# ArduinoRadioPC68XL.net
KiCad netlist of a schematic drawn in EAGLE
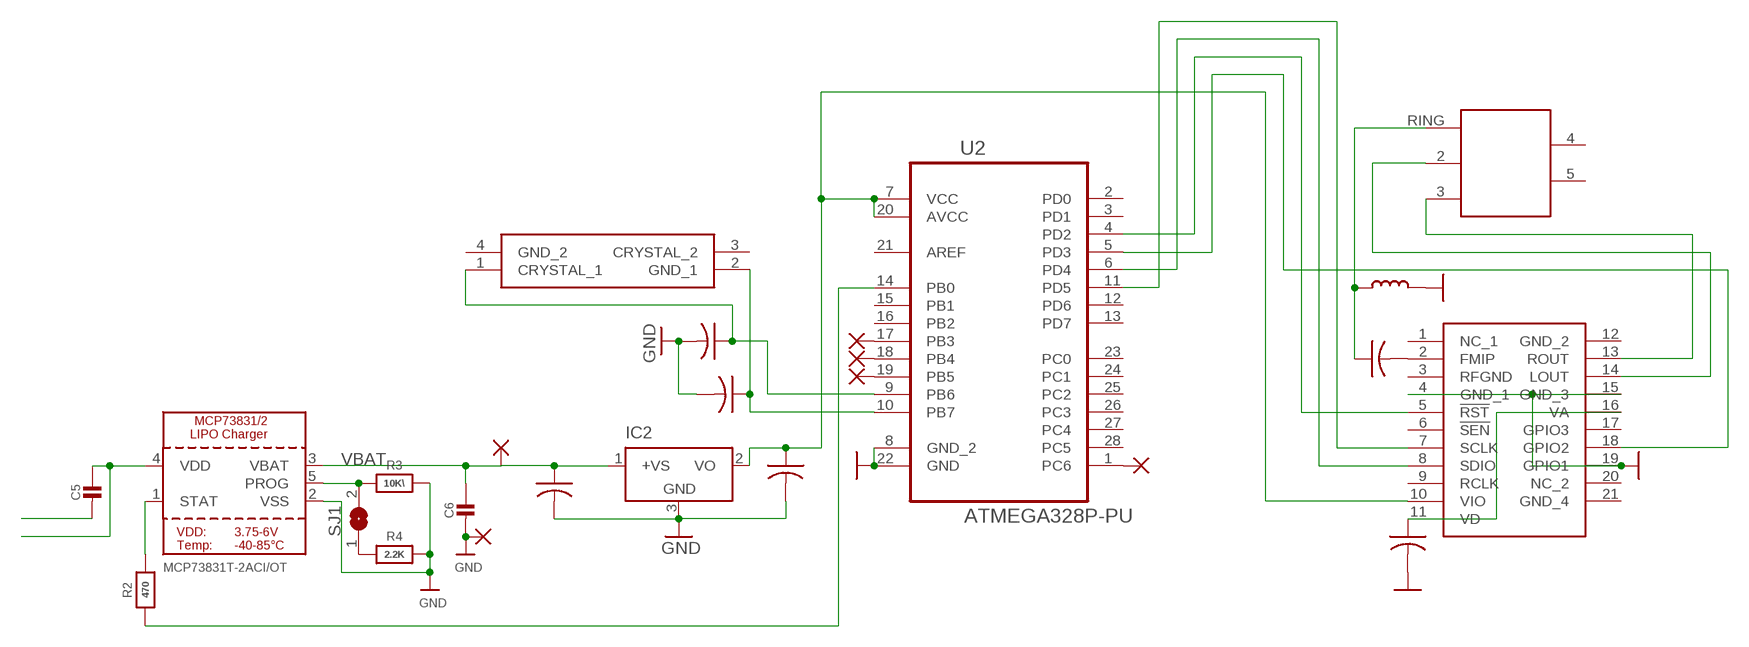
[diagram p0: schematic, sheet 1]

(export (version "E")
  (design (tool "Eeschema 10.0.6"))
  (components
    (comp (ref "C1")
      (value "10pF")
      (footprint "eagle-import:C0402")
      (libsource (lib "eagle-import") (part "rcl_334_C-USC0402"))
    )
    (comp (ref "C2")
      (value "10pF")
      (footprint "eagle-import:C0402")
      (libsource (lib "eagle-import") (part "rcl_334_C-USC0402"))
    )
    (comp (ref "C3")
      (value "47uf")
      (footprint "eagle-import:C1206")
      (libsource (lib "eagle-import") (part "better14pin_C-USC1206"))
    )
    (comp (ref "C4")
      (value "47uF")
      (footprint "eagle-import:C1206")
      (libsource (lib "eagle-import") (part "better14pin_C-USC1206"))
    )
    (comp (ref "C5")
      (value "10µF")
      (footprint "eagle-import:0805-NO@1")
      (libsource (lib "eagle-import") (part "CAP_CERAMIC0805-NOOUTLINE"))
    )
    (comp (ref "C6")
      (value "10µF")
      (footprint "eagle-import:0805-NO@1")
      (libsource (lib "eagle-import") (part "CAP_CERAMIC0805-NOOUTLINE"))
    )
    (comp (ref "C7")
      (value "22nF")
      (footprint "eagle-import:C0603")
      (libsource (lib "eagle-import") (part "C-USC0603"))
    )
    (comp (ref "C8")
      (value "100pF")
      (footprint "eagle-import:C1206")
      (libsource (lib "eagle-import") (part "C-USC1206"))
    )
    (comp (ref "IC2")
      (value "LM50")
      (footprint "eagle-import:SOT23")
      (libsource (lib "eagle-import") (part "LM50"))
    )
    (comp (ref "IC3")
      (value "SI4703-C19-GM")
      (footprint "eagle-import:SI4703C19GM")
      (fields
        (field (name "MANUFACTURER_PART_NUMBER") "Si4703-C19-GM")
        (field (name "MOUSER_PART_NUMBER") "634-SI4703-C19-GM")
      )
      (libsource (lib "eagle-import") (part "SI4703-C19-GM"))
    )
    (comp (ref "L1")
      (value "L_0603")
      (footprint "eagle-import:L0603")
      (libsource (lib "eagle-import") (part "L_0603"))
    )
    (comp (ref "PAD1")
      (value "WIREPADSMD1,27-254")
      (footprint "eagle-import:SMD1,27-2,54")
      (libsource (lib "eagle-import") (part "WIREPADSMD1,27-254"))
    )
    (comp (ref "PAD2")
      (value "WIREPADSMD1,27-254")
      (footprint "eagle-import:SMD1,27-2,54")
      (libsource (lib "eagle-import") (part "WIREPADSMD1,27-254"))
    )
    (comp (ref "PAD3")
      (value "SMD2")
      (footprint "eagle-import:SMD1,27-2,54")
      (libsource (lib "eagle-import") (part "SMD2"))
    )
    (comp (ref "PAD4")
      (value "SMD2")
      (footprint "eagle-import:SMD1,27-2,54")
      (libsource (lib "eagle-import") (part "SMD2"))
    )
    (comp (ref "PAD5")
      (value "SMD2")
      (footprint "eagle-import:SMD1,27-2,54")
      (libsource (lib "eagle-import") (part "SMD2"))
    )
    (comp (ref "PAD6")
      (value "SMD2")
      (footprint "eagle-import:SMD1,27-2,54")
      (libsource (lib "eagle-import") (part "SMD2"))
    )
    (comp (ref "R2")
      (value "470")
      (footprint "eagle-import:0603-NO")
      (libsource (lib "eagle-import") (part "RESISTOR_0603_NOOUT"))
    )
    (comp (ref "R3")
      (value "10K\\")
      (footprint "eagle-import:0603-NO")
      (libsource (lib "eagle-import") (part "RESISTOR_0603_NOOUT"))
    )
    (comp (ref "R4")
      (value "2.2K")
      (footprint "eagle-import:0603-NO")
      (libsource (lib "eagle-import") (part "RESISTOR_0603_NOOUT"))
    )
    (comp (ref "SJ1")
      (value "SOLDERJUMPER")
      (footprint "eagle-import:SOLDERJUMPER_ARROW_NOPASTE")
      (libsource (lib "eagle-import") (part "SOLDERJUMPER"))
    )
    (comp (ref "U$1")
      (value "STX-3542-5N-G-TR")
      (footprint "eagle-import:STX-3542-5N-G-TR")
      (libsource (lib "eagle-import") (part "STX-3542-5N-G-TR"))
    )
    (comp (ref "U1")
      (value "MCP73831T-2ACI/OT")
      (footprint "eagle-import:SOT23-5")
      (libsource (lib "eagle-import") (part "MCP73831/2"))
    )
    (comp (ref "U2")
      (value "ATMEGA328P-PU")
      (footprint "eagle-import:DIP254P762X457-28")
      (fields (field (name "MF") "Microchip"))
      (libsource (lib "eagle-import") (part "ATMEGA328P-PU"))
    )
    (comp (ref "Y1")
      (value "ABM3B-8.000MHZ-10-1-U-T")
      (footprint "eagle-import:ABM3B")
      (fields (field (name "MOUSER_PART_NUMBER") "815-ABM3B8MHZ101UT"))
      (libsource (lib "eagle-import") (part "ABM3B-8.000MHZ-10-1-U-T"))
    )
  )
  (nets
    (net (code "1") (name "/STAT") (class "Default")
      (node (ref "R2") (pin "1") (pinfunction "1_1") (pintype "passive"))
      (node (ref "R2") (pin "2") (pinfunction "2_2") (pintype "passive"))
      (node (ref "U1") (pin "1") (pinfunction "STAT_1") (pintype "output"))
      (node (ref "U2") (pin "14") (pinfunction "PB0_14") (pintype "bidirectional"))
    )
    (net (code "2") (name "/VBAT") (class "Default")
      (node (ref "C3") (pin "1") (pinfunction "1_1") (pintype "passive"))
      (node (ref "C6") (pin "1") (pinfunction "1_1") (pintype "passive"))
      (node (ref "C7") (pin "1") (pinfunction "1_1") (pintype "passive"))
      (node (ref "IC2") (pin "1") (pinfunction "+VS_1") (pintype "input"))
      (node (ref "IC3") (pin "11") (pinfunction "VD_11") (pintype "bidirectional"))
      (node (ref "IC3") (pin "16") (pinfunction "VA_16") (pintype "bidirectional"))
      (node (ref "PAD1") (pin "1") (pinfunction "P_1") (pintype "passive"))
      (node (ref "U1") (pin "3") (pinfunction "VBAT_3") (pintype "power_in"))
    )
    (net (code "3") (name "GND") (class "Default")
      (node (ref "C1") (pin "2") (pinfunction "2_2") (pintype "passive"))
      (node (ref "C2") (pin "2") (pinfunction "2_2") (pintype "passive"))
      (node (ref "C3") (pin "2") (pinfunction "2_2") (pintype "passive"))
      (node (ref "C4") (pin "2") (pinfunction "2_2") (pintype "passive"))
      (node (ref "C5") (pin "2") (pinfunction "2_2") (pintype "passive"))
      (node (ref "C6") (pin "2") (pinfunction "2_2") (pintype "passive"))
      (node (ref "C7") (pin "2") (pinfunction "2_2") (pintype "passive"))
      (node (ref "IC2") (pin "3") (pinfunction "GND_3") (pintype "power_in"))
      (node (ref "IC3") (pin "15") (pinfunction "GND_3_15") (pintype "bidirectional"))
      (node (ref "IC3") (pin "19") (pinfunction "GPIO1_19") (pintype "bidirectional"))
      (node (ref "IC3") (pin "4") (pinfunction "GND_1_4") (pintype "bidirectional"))
      (node (ref "L1") (pin "1") (pinfunction "1_1") (pintype "passive"))
      (node (ref "PAD2") (pin "1") (pinfunction "P_1") (pintype "passive"))
      (node (ref "R3") (pin "2") (pinfunction "2_2") (pintype "passive"))
      (node (ref "R4") (pin "2") (pinfunction "2_2") (pintype "passive"))
      (node (ref "U1") (pin "2") (pinfunction "VSS_2") (pintype "power_in"))
      (node (ref "U2") (pin "22") (pinfunction "GND_22") (pintype "passive"))
      (node (ref "U2") (pin "8") (pinfunction "GND_2_8") (pintype "passive"))
    )
    (net (code "4") (name "Net-(C8-Pad1)") (class "Default")
      (node (ref "C8") (pin "1") (pinfunction "1_1") (pintype "passive"))
      (node (ref "L1") (pin "2") (pinfunction "2_2") (pintype "passive"))
      (node (ref "U$1") (pin "RING") (pinfunction "RING_RING") (pintype "bidirectional"))
    )
    (net (code "5") (name "Net-(IC2-VO)") (class "Default")
      (node (ref "C4") (pin "1") (pinfunction "1_1") (pintype "passive"))
      (node (ref "IC2") (pin "2") (pinfunction "VO_2") (pintype "input"))
      (node (ref "IC3") (pin "10") (pinfunction "VIO_10") (pintype "bidirectional"))
      (node (ref "U2") (pin "20") (pinfunction "AVCC_20") (pintype "power_in"))
      (node (ref "U2") (pin "7") (pinfunction "VCC_7") (pintype "power_in"))
    )
    (net (code "6") (name "Net-(IC3-FMIP)") (class "Default")
      (node (ref "C8") (pin "2") (pinfunction "2_2") (pintype "passive"))
      (node (ref "IC3") (pin "2") (pinfunction "FMIP_2") (pintype "bidirectional"))
    )
    (net (code "7") (name "Net-(IC3-GPIO2)") (class "Default")
      (node (ref "IC3") (pin "18") (pinfunction "GPIO2_18") (pintype "bidirectional"))
      (node (ref "U2") (pin "5") (pinfunction "PD3_5") (pintype "bidirectional"))
    )
    (net (code "8") (name "Net-(IC3-LOUT)") (class "Default")
      (node (ref "IC3") (pin "14") (pinfunction "LOUT_14") (pintype "bidirectional"))
      (node (ref "U$1") (pin "2") (pinfunction "2_2") (pintype "bidirectional"))
    )
    (net (code "9") (name "Net-(IC3-ROUT)") (class "Default")
      (node (ref "IC3") (pin "13") (pinfunction "ROUT_13") (pintype "bidirectional"))
      (node (ref "U$1") (pin "3") (pinfunction "3_3") (pintype "bidirectional"))
    )
    (net (code "10") (name "Net-(IC3-SCLK)") (class "Default")
      (node (ref "IC3") (pin "7") (pinfunction "SCLK_7") (pintype "bidirectional"))
      (node (ref "U2") (pin "11") (pinfunction "PD5_11") (pintype "bidirectional"))
    )
    (net (code "11") (name "Net-(IC3-SDIO)") (class "Default")
      (node (ref "IC3") (pin "8") (pinfunction "SDIO_8") (pintype "bidirectional"))
      (node (ref "U2") (pin "6") (pinfunction "PD4_6") (pintype "bidirectional"))
    )
    (net (code "12") (name "Net-(IC3-~{RST})") (class "Default")
      (node (ref "IC3") (pin "5") (pinfunction "~{RST}_5") (pintype "bidirectional"))
      (node (ref "U2") (pin "4") (pinfunction "PD2_4") (pintype "bidirectional"))
    )
    (net (code "13") (name "Net-(PAD3-P)") (class "Default")
      (node (ref "PAD3") (pin "1") (pinfunction "P_1") (pintype "passive"))
      (node (ref "U2") (pin "1") (pinfunction "PC6_1") (pintype "bidirectional"))
    )
    (net (code "14") (name "Net-(PAD4-P)") (class "Default")
      (node (ref "PAD4") (pin "1") (pinfunction "P_1") (pintype "passive"))
      (node (ref "U2") (pin "19") (pinfunction "PB5_19") (pintype "bidirectional"))
    )
    (net (code "15") (name "Net-(PAD5-P)") (class "Default")
      (node (ref "PAD5") (pin "1") (pinfunction "P_1") (pintype "passive"))
      (node (ref "U2") (pin "18") (pinfunction "PB4_18") (pintype "bidirectional"))
    )
    (net (code "16") (name "Net-(PAD6-P)") (class "Default")
      (node (ref "PAD6") (pin "1") (pinfunction "P_1") (pintype "passive"))
      (node (ref "U2") (pin "17") (pinfunction "PB3_17") (pintype "bidirectional"))
    )
    (net (code "17") (name "Net-(R4-Pad1)") (class "Default")
      (node (ref "R4") (pin "1") (pinfunction "1_1") (pintype "passive"))
      (node (ref "SJ1") (pin "1") (pinfunction "1_1") (pintype "passive"))
    )
    (net (code "18") (name "Net-(U1-PROG)") (class "Default")
      (node (ref "R3") (pin "1") (pinfunction "1_1") (pintype "passive"))
      (node (ref "SJ1") (pin "2") (pinfunction "2_2") (pintype "passive"))
      (node (ref "U1") (pin "5") (pinfunction "PROG_5") (pintype "input"))
    )
    (net (code "19") (name "Net-(U1-VDD)") (class "Default")
      (node (ref "C5") (pin "1") (pinfunction "1_1") (pintype "passive"))
      (node (ref "U1") (pin "4") (pinfunction "VDD_4") (pintype "power_in"))
    )
    (net (code "20") (name "Net-(U2-PB6)") (class "Default")
      (node (ref "C2") (pin "1") (pinfunction "1_1") (pintype "passive"))
      (node (ref "U2") (pin "9") (pinfunction "PB6_9") (pintype "bidirectional"))
      (node (ref "Y1") (pin "1") (pinfunction "CRYSTAL_1_1") (pintype "bidirectional"))
    )
    (net (code "21") (name "Net-(U2-PB7)") (class "Default")
      (node (ref "C1") (pin "1") (pinfunction "1_1") (pintype "passive"))
      (node (ref "U2") (pin "10") (pinfunction "PB7_10") (pintype "bidirectional"))
      (node (ref "Y1") (pin "2") (pinfunction "GND_1_2") (pintype "bidirectional"))
    )
    (net (code "22") (name "unconnected-(IC3-GND_2-Pad12)") (class "Default")
      (node (ref "IC3") (pin "12") (pinfunction "GND_2_12") (pintype "bidirectional"))
    )
    (net (code "23") (name "unconnected-(IC3-GND_4-Pad21)") (class "Default")
      (node (ref "IC3") (pin "21") (pinfunction "GND_4_21") (pintype "bidirectional"))
    )
    (net (code "24") (name "unconnected-(IC3-GPIO3-Pad17)") (class "Default")
      (node (ref "IC3") (pin "17") (pinfunction "GPIO3_17") (pintype "bidirectional"))
    )
    (net (code "25") (name "unconnected-(IC3-NC_1-Pad1)") (class "Default")
      (node (ref "IC3") (pin "1") (pinfunction "NC_1_1") (pintype "bidirectional"))
    )
    (net (code "26") (name "unconnected-(IC3-NC_2-Pad20)") (class "Default")
      (node (ref "IC3") (pin "20") (pinfunction "NC_2_20") (pintype "bidirectional"))
    )
    (net (code "27") (name "unconnected-(IC3-RCLK-Pad9)") (class "Default")
      (node (ref "IC3") (pin "9") (pinfunction "RCLK_9") (pintype "bidirectional"))
    )
    (net (code "28") (name "unconnected-(IC3-RFGND-Pad3)") (class "Default")
      (node (ref "IC3") (pin "3") (pinfunction "RFGND_3") (pintype "bidirectional"))
    )
    (net (code "29") (name "unconnected-(IC3-~{SEN}-Pad6)") (class "Default")
      (node (ref "IC3") (pin "6") (pinfunction "~{SEN}_6") (pintype "bidirectional"))
    )
    (net (code "30") (name "unconnected-(U$1-Pad4)") (class "Default")
      (node (ref "U$1") (pin "4") (pinfunction "4_4") (pintype "bidirectional"))
    )
    (net (code "31") (name "unconnected-(U$1-Pad5)") (class "Default")
      (node (ref "U$1") (pin "5") (pinfunction "5_5") (pintype "bidirectional"))
    )
    (net (code "32") (name "unconnected-(U2-AREF-Pad21)") (class "Default")
      (node (ref "U2") (pin "21") (pinfunction "AREF_21") (pintype "input"))
    )
    (net (code "33") (name "unconnected-(U2-PB1-Pad15)") (class "Default")
      (node (ref "U2") (pin "15") (pinfunction "PB1_15") (pintype "bidirectional"))
    )
    (net (code "34") (name "unconnected-(U2-PB2-Pad16)") (class "Default")
      (node (ref "U2") (pin "16") (pinfunction "PB2_16") (pintype "bidirectional"))
    )
    (net (code "35") (name "unconnected-(U2-PC0-Pad23)") (class "Default")
      (node (ref "U2") (pin "23") (pinfunction "PC0_23") (pintype "bidirectional"))
    )
    (net (code "36") (name "unconnected-(U2-PC1-Pad24)") (class "Default")
      (node (ref "U2") (pin "24") (pinfunction "PC1_24") (pintype "bidirectional"))
    )
    (net (code "37") (name "unconnected-(U2-PC2-Pad25)") (class "Default")
      (node (ref "U2") (pin "25") (pinfunction "PC2_25") (pintype "bidirectional"))
    )
    (net (code "38") (name "unconnected-(U2-PC3-Pad26)") (class "Default")
      (node (ref "U2") (pin "26") (pinfunction "PC3_26") (pintype "bidirectional"))
    )
    (net (code "39") (name "unconnected-(U2-PC4-Pad27)") (class "Default")
      (node (ref "U2") (pin "27") (pinfunction "PC4_27") (pintype "bidirectional"))
    )
    (net (code "40") (name "unconnected-(U2-PC5-Pad28)") (class "Default")
      (node (ref "U2") (pin "28") (pinfunction "PC5_28") (pintype "bidirectional"))
    )
    (net (code "41") (name "unconnected-(U2-PD0-Pad2)") (class "Default")
      (node (ref "U2") (pin "2") (pinfunction "PD0_2") (pintype "bidirectional"))
    )
    (net (code "42") (name "unconnected-(U2-PD1-Pad3)") (class "Default")
      (node (ref "U2") (pin "3") (pinfunction "PD1_3") (pintype "bidirectional"))
    )
    (net (code "43") (name "unconnected-(U2-PD6-Pad12)") (class "Default")
      (node (ref "U2") (pin "12") (pinfunction "PD6_12") (pintype "bidirectional"))
    )
    (net (code "44") (name "unconnected-(U2-PD7-Pad13)") (class "Default")
      (node (ref "U2") (pin "13") (pinfunction "PD7_13") (pintype "bidirectional"))
    )
    (net (code "45") (name "unconnected-(Y1-CRYSTAL_2-Pad3)") (class "Default")
      (node (ref "Y1") (pin "3") (pinfunction "CRYSTAL_2_3") (pintype "bidirectional"))
    )
    (net (code "46") (name "unconnected-(Y1-GND_2-Pad4)") (class "Default")
      (node (ref "Y1") (pin "4") (pinfunction "GND_2_4") (pintype "bidirectional"))
    )
  )
)
